# xmas_v3.net
KiCad netlist of a schematic drawn in EAGLE
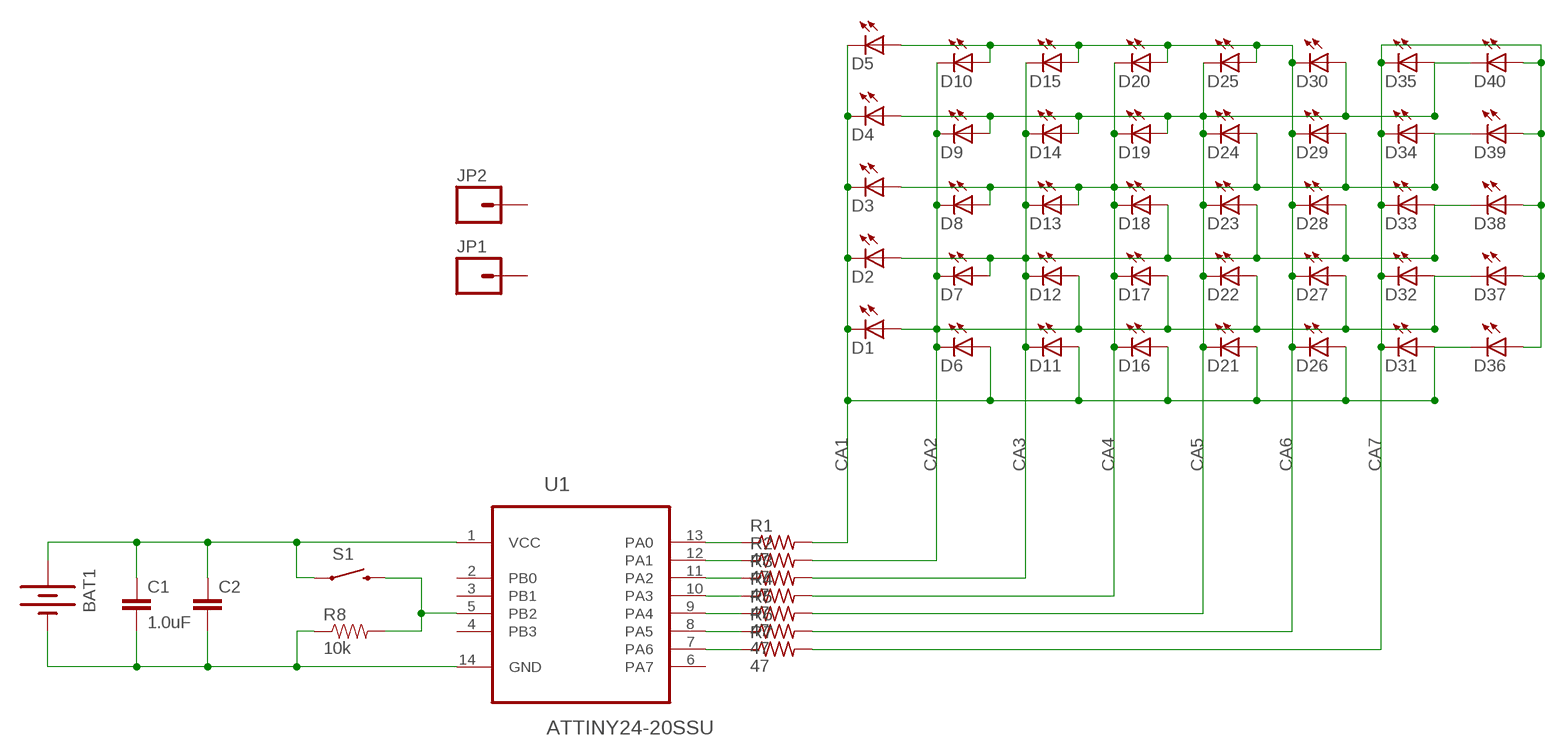
[diagram p0: schematic, sheet 1]

(export (version "E")
  (design (tool "Eeschema 10.0.6"))
  (components
    (comp (ref "BAT1")
      (value "BATTERY20PTH")
      (footprint "eagle-import:BATTCOM_20MM_PTH")
      (libsource (lib "eagle-import") (part "BATTERY20PTH"))
    )
    (comp (ref "C1")
      (value "1.0uF")
      (footprint "eagle-import:0805-CAP")
      (libsource (lib "eagle-import") (part "1.0UF-25V-+80/-20(0805){dblquote}"))
    )
    (comp (ref "C2")
      (value "CAP0805")
      (footprint "eagle-import:0805")
      (libsource (lib "eagle-import") (part "CAP0805"))
    )
    (comp (ref "D1")
      (value "LEDCHIP-LED0603")
      (footprint "eagle-import:CHIP-LED0603")
      (libsource (lib "eagle-import") (part "LEDCHIP-LED0603"))
    )
    (comp (ref "D2")
      (value "LEDCHIP-LED0603")
      (footprint "eagle-import:CHIP-LED0603")
      (libsource (lib "eagle-import") (part "LEDCHIP-LED0603"))
    )
    (comp (ref "D3")
      (value "LEDCHIP-LED0603")
      (footprint "eagle-import:CHIP-LED0603")
      (libsource (lib "eagle-import") (part "LEDCHIP-LED0603"))
    )
    (comp (ref "D4")
      (value "LEDCHIP-LED0603")
      (footprint "eagle-import:CHIP-LED0603")
      (libsource (lib "eagle-import") (part "LEDCHIP-LED0603"))
    )
    (comp (ref "D5")
      (value "LEDCHIP-LED0603")
      (footprint "eagle-import:CHIP-LED0603")
      (libsource (lib "eagle-import") (part "LEDCHIP-LED0603"))
    )
    (comp (ref "D6")
      (value "LEDCHIP-LED0603")
      (footprint "eagle-import:CHIP-LED0603")
      (libsource (lib "eagle-import") (part "LEDCHIP-LED0603"))
    )
    (comp (ref "D7")
      (value "LEDCHIP-LED0603")
      (footprint "eagle-import:CHIP-LED0603")
      (libsource (lib "eagle-import") (part "LEDCHIP-LED0603"))
    )
    (comp (ref "D8")
      (value "LEDCHIP-LED0603")
      (footprint "eagle-import:CHIP-LED0603")
      (libsource (lib "eagle-import") (part "LEDCHIP-LED0603"))
    )
    (comp (ref "D9")
      (value "LEDCHIP-LED0603")
      (footprint "eagle-import:CHIP-LED0603")
      (libsource (lib "eagle-import") (part "LEDCHIP-LED0603"))
    )
    (comp (ref "D10")
      (value "LEDCHIP-LED0603")
      (footprint "eagle-import:CHIP-LED0603")
      (libsource (lib "eagle-import") (part "LEDCHIP-LED0603"))
    )
    (comp (ref "D11")
      (value "LEDCHIP-LED0603")
      (footprint "eagle-import:CHIP-LED0603")
      (libsource (lib "eagle-import") (part "LEDCHIP-LED0603"))
    )
    (comp (ref "D12")
      (value "LEDCHIP-LED0603")
      (footprint "eagle-import:CHIP-LED0603")
      (libsource (lib "eagle-import") (part "LEDCHIP-LED0603"))
    )
    (comp (ref "D13")
      (value "LEDCHIP-LED0603")
      (footprint "eagle-import:CHIP-LED0603")
      (libsource (lib "eagle-import") (part "LEDCHIP-LED0603"))
    )
    (comp (ref "D14")
      (value "LEDCHIP-LED0603")
      (footprint "eagle-import:CHIP-LED0603")
      (libsource (lib "eagle-import") (part "LEDCHIP-LED0603"))
    )
    (comp (ref "D15")
      (value "LEDCHIP-LED0603")
      (footprint "eagle-import:CHIP-LED0603")
      (libsource (lib "eagle-import") (part "LEDCHIP-LED0603"))
    )
    (comp (ref "D16")
      (value "LEDCHIP-LED0603")
      (footprint "eagle-import:CHIP-LED0603")
      (libsource (lib "eagle-import") (part "LEDCHIP-LED0603"))
    )
    (comp (ref "D17")
      (value "LEDCHIP-LED0603")
      (footprint "eagle-import:CHIP-LED0603")
      (libsource (lib "eagle-import") (part "LEDCHIP-LED0603"))
    )
    (comp (ref "D18")
      (value "LEDCHIP-LED0603")
      (footprint "eagle-import:CHIP-LED0603")
      (libsource (lib "eagle-import") (part "LEDCHIP-LED0603"))
    )
    (comp (ref "D19")
      (value "LEDCHIP-LED0603")
      (footprint "eagle-import:CHIP-LED0603")
      (libsource (lib "eagle-import") (part "LEDCHIP-LED0603"))
    )
    (comp (ref "D20")
      (value "LEDCHIP-LED0603")
      (footprint "eagle-import:CHIP-LED0603")
      (libsource (lib "eagle-import") (part "LEDCHIP-LED0603"))
    )
    (comp (ref "D21")
      (value "LEDCHIP-LED0603")
      (footprint "eagle-import:CHIP-LED0603")
      (libsource (lib "eagle-import") (part "LEDCHIP-LED0603"))
    )
    (comp (ref "D22")
      (value "LEDCHIP-LED0603")
      (footprint "eagle-import:CHIP-LED0603")
      (libsource (lib "eagle-import") (part "LEDCHIP-LED0603"))
    )
    (comp (ref "D23")
      (value "LEDCHIP-LED0603")
      (footprint "eagle-import:CHIP-LED0603")
      (libsource (lib "eagle-import") (part "LEDCHIP-LED0603"))
    )
    (comp (ref "D24")
      (value "LEDCHIP-LED0603")
      (footprint "eagle-import:CHIP-LED0603")
      (libsource (lib "eagle-import") (part "LEDCHIP-LED0603"))
    )
    (comp (ref "D25")
      (value "LEDCHIP-LED0603")
      (footprint "eagle-import:CHIP-LED0603")
      (libsource (lib "eagle-import") (part "LEDCHIP-LED0603"))
    )
    (comp (ref "D26")
      (value "LEDCHIP-LED0603")
      (footprint "eagle-import:CHIP-LED0603")
      (libsource (lib "eagle-import") (part "LEDCHIP-LED0603"))
    )
    (comp (ref "D27")
      (value "LEDCHIP-LED0603")
      (footprint "eagle-import:CHIP-LED0603")
      (libsource (lib "eagle-import") (part "LEDCHIP-LED0603"))
    )
    (comp (ref "D28")
      (value "LEDCHIP-LED0603")
      (footprint "eagle-import:CHIP-LED0603")
      (libsource (lib "eagle-import") (part "LEDCHIP-LED0603"))
    )
    (comp (ref "D29")
      (value "LEDCHIP-LED0603")
      (footprint "eagle-import:CHIP-LED0603")
      (libsource (lib "eagle-import") (part "LEDCHIP-LED0603"))
    )
    (comp (ref "D30")
      (value "LEDCHIP-LED0603")
      (footprint "eagle-import:CHIP-LED0603")
      (libsource (lib "eagle-import") (part "LEDCHIP-LED0603"))
    )
    (comp (ref "D31")
      (value "LEDCHIP-LED0603")
      (footprint "eagle-import:CHIP-LED0603")
      (libsource (lib "eagle-import") (part "LEDCHIP-LED0603"))
    )
    (comp (ref "D32")
      (value "LEDCHIP-LED0603")
      (footprint "eagle-import:CHIP-LED0603")
      (libsource (lib "eagle-import") (part "LEDCHIP-LED0603"))
    )
    (comp (ref "D33")
      (value "LEDCHIP-LED0603")
      (footprint "eagle-import:CHIP-LED0603")
      (libsource (lib "eagle-import") (part "LEDCHIP-LED0603"))
    )
    (comp (ref "D34")
      (value "LEDCHIP-LED0603")
      (footprint "eagle-import:CHIP-LED0603")
      (libsource (lib "eagle-import") (part "LEDCHIP-LED0603"))
    )
    (comp (ref "D35")
      (value "LEDCHIP-LED0603")
      (footprint "eagle-import:CHIP-LED0603")
      (libsource (lib "eagle-import") (part "LEDCHIP-LED0603"))
    )
    (comp (ref "D36")
      (value "LEDCHIP-LED0603")
      (footprint "eagle-import:CHIP-LED0603")
      (libsource (lib "eagle-import") (part "LEDCHIP-LED0603"))
    )
    (comp (ref "D37")
      (value "LEDCHIP-LED0603")
      (footprint "eagle-import:CHIP-LED0603")
      (libsource (lib "eagle-import") (part "LEDCHIP-LED0603"))
    )
    (comp (ref "D38")
      (value "LEDCHIP-LED0603")
      (footprint "eagle-import:CHIP-LED0603")
      (libsource (lib "eagle-import") (part "LEDCHIP-LED0603"))
    )
    (comp (ref "D39")
      (value "LEDCHIP-LED0603")
      (footprint "eagle-import:CHIP-LED0603")
      (libsource (lib "eagle-import") (part "LEDCHIP-LED0603"))
    )
    (comp (ref "D40")
      (value "LEDCHIP-LED0603")
      (footprint "eagle-import:CHIP-LED0603")
      (libsource (lib "eagle-import") (part "LEDCHIP-LED0603"))
    )
    (comp (ref "JP1")
      (value "M01PTH_NO_SILK_YES_STOP")
      (footprint "eagle-import:1X01_NO_SILK")
      (libsource (lib "eagle-import") (part "M01PTH_NO_SILK_YES_STOP"))
    )
    (comp (ref "JP2")
      (value "M01PTH_NO_SILK_YES_STOP")
      (footprint "eagle-import:1X01_NO_SILK")
      (libsource (lib "eagle-import") (part "M01PTH_NO_SILK_YES_STOP"))
    )
    (comp (ref "R1")
      (value "47")
      (footprint "eagle-import:R0603")
      (libsource (lib "eagle-import") (part "R-US_R0603"))
    )
    (comp (ref "R2")
      (value "47")
      (footprint "eagle-import:R0603")
      (libsource (lib "eagle-import") (part "R-US_R0603"))
    )
    (comp (ref "R3")
      (value "47")
      (footprint "eagle-import:R0603")
      (libsource (lib "eagle-import") (part "R-US_R0603"))
    )
    (comp (ref "R4")
      (value "47")
      (footprint "eagle-import:R0603")
      (libsource (lib "eagle-import") (part "R-US_R0603"))
    )
    (comp (ref "R5")
      (value "47")
      (footprint "eagle-import:R0603")
      (libsource (lib "eagle-import") (part "R-US_R0603"))
    )
    (comp (ref "R6")
      (value "47")
      (footprint "eagle-import:R0603")
      (libsource (lib "eagle-import") (part "R-US_R0603"))
    )
    (comp (ref "R7")
      (value "47")
      (footprint "eagle-import:R0603")
      (libsource (lib "eagle-import") (part "R-US_R0603"))
    )
    (comp (ref "R8")
      (value "10k")
      (footprint "eagle-import:0805")
      (libsource (lib "eagle-import") (part "RESISTOR0805-RES"))
    )
    (comp (ref "S1")
      (value "SWITCH-MOMENTARY-2SMD-4")
      (footprint "eagle-import:TACTILE_SWITCH_TALL")
      (libsource (lib "eagle-import") (part "SWITCH-MOMENTARY-2SMD-4"))
    )
    (comp (ref "U1")
      (value "ATTINY24-20SSU")
      (footprint "eagle-import:SOIC127P600X175-14N")
      (libsource (lib "eagle-import") (part "ATTINY24-20SSU"))
    )
  )
  (nets
    (net (code "1") (name "/CA1") (class "Default")
      (node (ref "D1") (pin "C") (pinfunction "C_C") (pintype "passive"))
      (node (ref "D11") (pin "A") (pinfunction "A_A") (pintype "passive"))
      (node (ref "D16") (pin "A") (pinfunction "A_A") (pintype "passive"))
      (node (ref "D2") (pin "C") (pinfunction "C_C") (pintype "passive"))
      (node (ref "D21") (pin "A") (pinfunction "A_A") (pintype "passive"))
      (node (ref "D26") (pin "A") (pinfunction "A_A") (pintype "passive"))
      (node (ref "D3") (pin "C") (pinfunction "C_C") (pintype "passive"))
      (node (ref "D31") (pin "A") (pinfunction "A_A") (pintype "passive"))
      (node (ref "D36") (pin "C") (pinfunction "C_C") (pintype "passive"))
      (node (ref "D4") (pin "C") (pinfunction "C_C") (pintype "passive"))
      (node (ref "D5") (pin "C") (pinfunction "C_C") (pintype "passive"))
      (node (ref "D6") (pin "A") (pinfunction "A_A") (pintype "passive"))
      (node (ref "R1") (pin "2") (pinfunction "2_2") (pintype "passive"))
    )
    (net (code "2") (name "/CA2") (class "Default")
      (node (ref "D1") (pin "A") (pinfunction "A_A") (pintype "passive"))
      (node (ref "D10") (pin "C") (pinfunction "C_C") (pintype "passive"))
      (node (ref "D12") (pin "A") (pinfunction "A_A") (pintype "passive"))
      (node (ref "D17") (pin "A") (pinfunction "A_A") (pintype "passive"))
      (node (ref "D22") (pin "A") (pinfunction "A_A") (pintype "passive"))
      (node (ref "D27") (pin "A") (pinfunction "A_A") (pintype "passive"))
      (node (ref "D32") (pin "A") (pinfunction "A_A") (pintype "passive"))
      (node (ref "D37") (pin "C") (pinfunction "C_C") (pintype "passive"))
      (node (ref "D6") (pin "C") (pinfunction "C_C") (pintype "passive"))
      (node (ref "D7") (pin "C") (pinfunction "C_C") (pintype "passive"))
      (node (ref "D8") (pin "C") (pinfunction "C_C") (pintype "passive"))
      (node (ref "D9") (pin "C") (pinfunction "C_C") (pintype "passive"))
      (node (ref "R2") (pin "2") (pinfunction "2_2") (pintype "passive"))
    )
    (net (code "3") (name "/CA3") (class "Default")
      (node (ref "D11") (pin "C") (pinfunction "C_C") (pintype "passive"))
      (node (ref "D12") (pin "C") (pinfunction "C_C") (pintype "passive"))
      (node (ref "D13") (pin "C") (pinfunction "C_C") (pintype "passive"))
      (node (ref "D14") (pin "C") (pinfunction "C_C") (pintype "passive"))
      (node (ref "D15") (pin "C") (pinfunction "C_C") (pintype "passive"))
      (node (ref "D18") (pin "A") (pinfunction "A_A") (pintype "passive"))
      (node (ref "D2") (pin "A") (pinfunction "A_A") (pintype "passive"))
      (node (ref "D23") (pin "A") (pinfunction "A_A") (pintype "passive"))
      (node (ref "D28") (pin "A") (pinfunction "A_A") (pintype "passive"))
      (node (ref "D33") (pin "A") (pinfunction "A_A") (pintype "passive"))
      (node (ref "D38") (pin "C") (pinfunction "C_C") (pintype "passive"))
      (node (ref "D7") (pin "A") (pinfunction "A_A") (pintype "passive"))
      (node (ref "R3") (pin "2") (pinfunction "2_2") (pintype "passive"))
    )
    (net (code "4") (name "/CA4") (class "Default")
      (node (ref "D13") (pin "A") (pinfunction "A_A") (pintype "passive"))
      (node (ref "D16") (pin "C") (pinfunction "C_C") (pintype "passive"))
      (node (ref "D17") (pin "C") (pinfunction "C_C") (pintype "passive"))
      (node (ref "D18") (pin "C") (pinfunction "C_C") (pintype "passive"))
      (node (ref "D19") (pin "C") (pinfunction "C_C") (pintype "passive"))
      (node (ref "D20") (pin "C") (pinfunction "C_C") (pintype "passive"))
      (node (ref "D24") (pin "A") (pinfunction "A_A") (pintype "passive"))
      (node (ref "D29") (pin "A") (pinfunction "A_A") (pintype "passive"))
      (node (ref "D3") (pin "A") (pinfunction "A_A") (pintype "passive"))
      (node (ref "D34") (pin "A") (pinfunction "A_A") (pintype "passive"))
      (node (ref "D39") (pin "C") (pinfunction "C_C") (pintype "passive"))
      (node (ref "D8") (pin "A") (pinfunction "A_A") (pintype "passive"))
      (node (ref "R4") (pin "2") (pinfunction "2_2") (pintype "passive"))
    )
    (net (code "5") (name "/CA5") (class "Default")
      (node (ref "D14") (pin "A") (pinfunction "A_A") (pintype "passive"))
      (node (ref "D19") (pin "A") (pinfunction "A_A") (pintype "passive"))
      (node (ref "D21") (pin "C") (pinfunction "C_C") (pintype "passive"))
      (node (ref "D22") (pin "C") (pinfunction "C_C") (pintype "passive"))
      (node (ref "D23") (pin "C") (pinfunction "C_C") (pintype "passive"))
      (node (ref "D24") (pin "C") (pinfunction "C_C") (pintype "passive"))
      (node (ref "D25") (pin "C") (pinfunction "C_C") (pintype "passive"))
      (node (ref "D30") (pin "A") (pinfunction "A_A") (pintype "passive"))
      (node (ref "D35") (pin "A") (pinfunction "A_A") (pintype "passive"))
      (node (ref "D4") (pin "A") (pinfunction "A_A") (pintype "passive"))
      (node (ref "D40") (pin "C") (pinfunction "C_C") (pintype "passive"))
      (node (ref "D9") (pin "A") (pinfunction "A_A") (pintype "passive"))
      (node (ref "R5") (pin "2") (pinfunction "2_2") (pintype "passive"))
    )
    (net (code "6") (name "/CA6") (class "Default")
      (node (ref "D10") (pin "A") (pinfunction "A_A") (pintype "passive"))
      (node (ref "D15") (pin "A") (pinfunction "A_A") (pintype "passive"))
      (node (ref "D20") (pin "A") (pinfunction "A_A") (pintype "passive"))
      (node (ref "D25") (pin "A") (pinfunction "A_A") (pintype "passive"))
      (node (ref "D26") (pin "C") (pinfunction "C_C") (pintype "passive"))
      (node (ref "D27") (pin "C") (pinfunction "C_C") (pintype "passive"))
      (node (ref "D28") (pin "C") (pinfunction "C_C") (pintype "passive"))
      (node (ref "D29") (pin "C") (pinfunction "C_C") (pintype "passive"))
      (node (ref "D30") (pin "C") (pinfunction "C_C") (pintype "passive"))
      (node (ref "D5") (pin "A") (pinfunction "A_A") (pintype "passive"))
      (node (ref "R6") (pin "2") (pinfunction "2_2") (pintype "passive"))
    )
    (net (code "7") (name "/CA7") (class "Default")
      (node (ref "D31") (pin "C") (pinfunction "C_C") (pintype "passive"))
      (node (ref "D32") (pin "C") (pinfunction "C_C") (pintype "passive"))
      (node (ref "D33") (pin "C") (pinfunction "C_C") (pintype "passive"))
      (node (ref "D34") (pin "C") (pinfunction "C_C") (pintype "passive"))
      (node (ref "D35") (pin "C") (pinfunction "C_C") (pintype "passive"))
      (node (ref "D36") (pin "A") (pinfunction "A_A") (pintype "passive"))
      (node (ref "D37") (pin "A") (pinfunction "A_A") (pintype "passive"))
      (node (ref "D38") (pin "A") (pinfunction "A_A") (pintype "passive"))
      (node (ref "D39") (pin "A") (pinfunction "A_A") (pintype "passive"))
      (node (ref "D40") (pin "A") (pinfunction "A_A") (pintype "passive"))
      (node (ref "R7") (pin "2") (pinfunction "2_2") (pintype "passive"))
    )
    (net (code "8") (name "Net-(BAT1-+)") (class "Default")
      (node (ref "BAT1") (pin "1") (pinfunction "+_1") (pintype "power_in"))
      (node (ref "C1") (pin "1") (pinfunction "1_1") (pintype "passive"))
      (node (ref "C2") (pin "1") (pinfunction "1_1") (pintype "passive"))
      (node (ref "S1") (pin "A2") (pinfunction "1_A2") (pintype "passive"))
      (node (ref "U1") (pin "1") (pinfunction "VCC_1") (pintype "power_in"))
    )
    (net (code "9") (name "Net-(BAT1--)") (class "Default")
      (node (ref "BAT1") (pin "2") (pinfunction "-_2") (pintype "power_in"))
      (node (ref "C1") (pin "2") (pinfunction "2_2") (pintype "passive"))
      (node (ref "C2") (pin "2") (pinfunction "2_2") (pintype "passive"))
      (node (ref "R8") (pin "1") (pinfunction "1_1") (pintype "passive"))
      (node (ref "U1") (pin "14") (pinfunction "GND_14") (pintype "passive"))
    )
    (net (code "10") (name "Net-(S1-2)") (class "Default")
      (node (ref "R8") (pin "2") (pinfunction "2_2") (pintype "passive"))
      (node (ref "S1") (pin "B2") (pinfunction "2_B2") (pintype "passive"))
      (node (ref "U1") (pin "5") (pinfunction "PB2_5") (pintype "bidirectional"))
    )
    (net (code "11") (name "Net-(U1-PA0)") (class "Default")
      (node (ref "R1") (pin "1") (pinfunction "1_1") (pintype "passive"))
      (node (ref "U1") (pin "13") (pinfunction "PA0_13") (pintype "bidirectional"))
    )
    (net (code "12") (name "Net-(U1-PA1)") (class "Default")
      (node (ref "R2") (pin "1") (pinfunction "1_1") (pintype "passive"))
      (node (ref "U1") (pin "12") (pinfunction "PA1_12") (pintype "bidirectional"))
    )
    (net (code "13") (name "Net-(U1-PA2)") (class "Default")
      (node (ref "R3") (pin "1") (pinfunction "1_1") (pintype "passive"))
      (node (ref "U1") (pin "11") (pinfunction "PA2_11") (pintype "bidirectional"))
    )
    (net (code "14") (name "Net-(U1-PA3)") (class "Default")
      (node (ref "R4") (pin "1") (pinfunction "1_1") (pintype "passive"))
      (node (ref "U1") (pin "10") (pinfunction "PA3_10") (pintype "bidirectional"))
    )
    (net (code "15") (name "Net-(U1-PA4)") (class "Default")
      (node (ref "R5") (pin "1") (pinfunction "1_1") (pintype "passive"))
      (node (ref "U1") (pin "9") (pinfunction "PA4_9") (pintype "bidirectional"))
    )
    (net (code "16") (name "Net-(U1-PA5)") (class "Default")
      (node (ref "R6") (pin "1") (pinfunction "1_1") (pintype "passive"))
      (node (ref "U1") (pin "8") (pinfunction "PA5_8") (pintype "bidirectional"))
    )
    (net (code "17") (name "Net-(U1-PA6)") (class "Default")
      (node (ref "R7") (pin "1") (pinfunction "1_1") (pintype "passive"))
      (node (ref "U1") (pin "7") (pinfunction "PA6_7") (pintype "bidirectional"))
    )
    (net (code "18") (name "unconnected-(JP1-Pad1)") (class "Default")
      (node (ref "JP1") (pin "1") (pinfunction "1_1") (pintype "passive"))
    )
    (net (code "19") (name "unconnected-(JP2-Pad1)") (class "Default")
      (node (ref "JP2") (pin "1") (pinfunction "1_1") (pintype "passive"))
    )
    (net (code "20") (name "unconnected-(U1-PA7-Pad6)") (class "Default")
      (node (ref "U1") (pin "6") (pinfunction "PA7_6") (pintype "bidirectional"))
    )
    (net (code "21") (name "unconnected-(U1-PB0-Pad2)") (class "Default")
      (node (ref "U1") (pin "2") (pinfunction "PB0_2") (pintype "bidirectional"))
    )
    (net (code "22") (name "unconnected-(U1-PB1-Pad3)") (class "Default")
      (node (ref "U1") (pin "3") (pinfunction "PB1_3") (pintype "bidirectional"))
    )
    (net (code "23") (name "unconnected-(U1-PB3-Pad4)") (class "Default")
      (node (ref "U1") (pin "4") (pinfunction "PB3_4") (pintype "bidirectional"))
    )
  )
)
